# Rev2_Schematic.net
KiCad netlist of a schematic drawn in EasyEDA
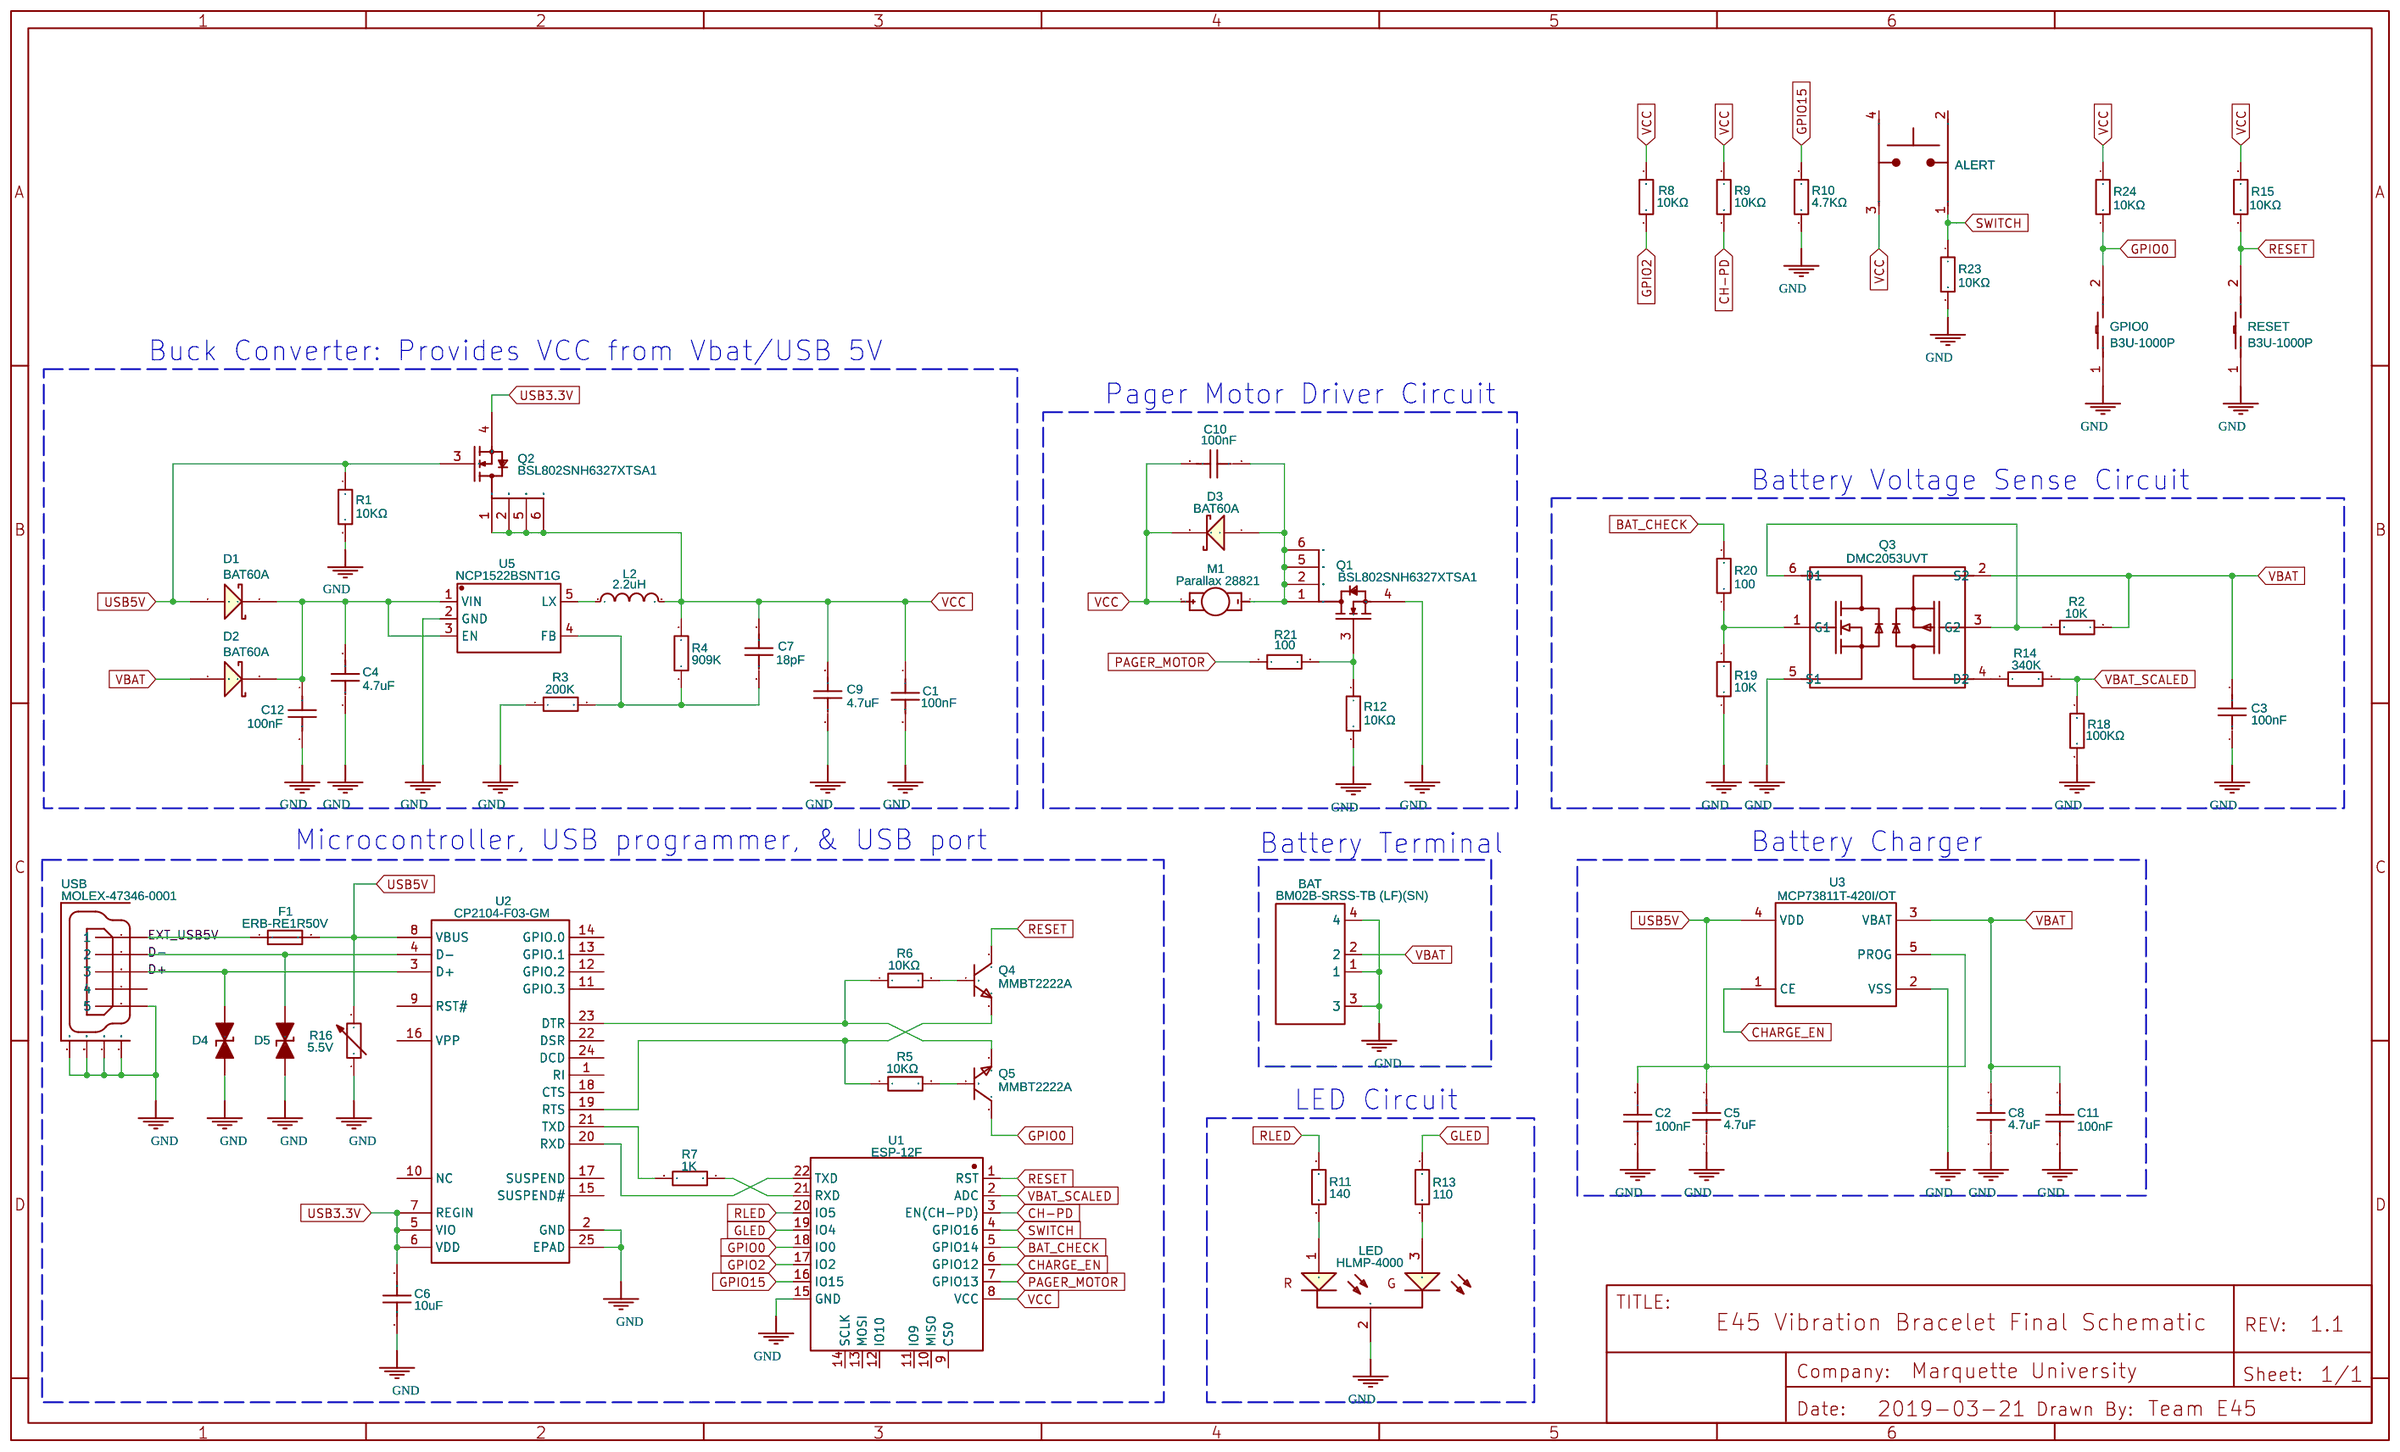
[diagram p0: schematic sheet]

(export (version "E")
  (design (tool "Eeschema 10.0.6"))
  (components
    (comp (ref "ALERT")
      (value "Pushbutton_SMD_SPST_2x2")
      (fields
        (field (name "BOM_Manufacturer Part") "LL3301NF065QG")
        (field (name "BOM_Supplier Part") "612-LL3301NF065QG")
      )
      (libsource (lib "") (part "Unknown_1070_100"))
    )
    (comp (ref "BAT")
      (value "BM02B-SRSS-TB (LF)(SN)")
      (fields
        (field (name "BOM_Manufacturer Part") "BM02B-SRSS-TB(LF)(SN)")
        (field (name "BOM_Supplier Part") "455-1788-1-ND")
      )
      (libsource (lib "") (part "Unknown_725_565"))
    )
    (comp (ref "C1")
      (value "100nF")
      (fields
        (field (name "BOM_Manufacturer Part") "0402YC104KAT2A")
        (field (name "BOM_Supplier Part") "581-0402YC104KAT2A")
      )
      (libsource (lib "") (part "Unknown_485_410"))
    )
    (comp (ref "C2")
      (value "100nF")
      (fields
        (field (name "BOM_Manufacturer Part") "0402YC104KAT2A")
        (field (name "BOM_Supplier Part") "581-0402YC104KAT2A")
      )
      (libsource (lib "") (part "Unknown_910_655"))
    )
    (comp (ref "C3")
      (value "100nF")
      (fields
        (field (name "BOM_Manufacturer Part") "0402YC104KAT2A")
        (field (name "BOM_Supplier Part") "581-0402YC104KAT2A")
      )
      (libsource (lib "") (part "Unknown_1255_420"))
    )
    (comp (ref "C4")
      (value "4.7uF")
      (fields
        (field (name "BOM_Manufacturer Part") "CC0402MRX5R7BB475")
        (field (name "BOM_Supplier Part") "603-CC0402MRX57BB475")
      )
      (libsource (lib "") (part "Unknown_160_400"))
    )
    (comp (ref "C5")
      (value "4.7uF")
      (fields
        (field (name "BOM_Manufacturer Part") "CC0402MRX5R7BB475")
        (field (name "BOM_Supplier Part") "603-CC0402MRX57BB475")
      )
      (libsource (lib "") (part "Unknown_950_655"))
    )
    (comp (ref "C6")
      (value "10uF")
      (fields
        (field (name "BOM_Manufacturer Part") "EMK107BBJ106MA-T")
        (field (name "BOM_Supplier Part") "C90058")
      )
      (libsource (lib "") (part "EMK107BBJ106MA-T"))
    )
    (comp (ref "C7")
      (value "18pF")
      (fields
        (field (name "BOM_Manufacturer Part") "C0402C180M5HACTU")
        (field (name "BOM_Supplier Part") "80-C0402C180M5HACTU")
      )
      (libsource (lib "") (part "Unknown_400_385"))
    )
    (comp (ref "C8")
      (value "4.7uF")
      (fields
        (field (name "BOM_Manufacturer Part") "CC0402MRX5R7BB475")
        (field (name "BOM_Supplier Part") "603-CC0402MRX57BB475")
      )
      (libsource (lib "") (part "Unknown_1115_655"))
    )
    (comp (ref "C9")
      (value "4.7uF")
      (fields
        (field (name "BOM_Manufacturer Part") "CC0402MRX5R7BB475")
        (field (name "BOM_Supplier Part") "603-CC0402MRX57BB475")
      )
      (libsource (lib "") (part "Unknown_440_410"))
    )
    (comp (ref "C10")
      (value "100nF")
      (fields
        (field (name "BOM_Manufacturer Part") "0402YC104KAT2A")
        (field (name "BOM_Supplier Part") "581-0402YC104KAT2A")
      )
      (libsource (lib "") (part "Unknown_665_275"))
    )
    (comp (ref "C11")
      (value "100nF")
      (fields
        (field (name "BOM_Manufacturer Part") "0402YC104KAT2A")
        (field (name "BOM_Supplier Part") "581-0402YC104KAT2A")
      )
      (libsource (lib "") (part "Unknown_1155_655"))
    )
    (comp (ref "C12")
      (value "100nF")
      (fields
        (field (name "BOM_Manufacturer Part") "0402YC104KAT2A")
        (field (name "BOM_Supplier Part") "581-0402YC104KAT2A")
      )
      (libsource (lib "") (part "Unknown_135_420"))
    )
    (comp (ref "D1")
      (value "BAT60A")
      (fields (field (name "BOM_Manufacturer Part") "?"))
      (libsource (lib "") (part "Unknown_95_355"))
    )
    (comp (ref "D2")
      (value "BAT60A")
      (fields (field (name "BOM_Manufacturer Part") "?"))
      (libsource (lib "") (part "Unknown_95_400"))
    )
    (comp (ref "D3")
      (value "BAT60A")
      (fields (field (name "BOM_Manufacturer Part") "?"))
      (libsource (lib "") (part "Unknown_665_315"))
    )
    (comp (ref "D4")
      (value "PGB1010402KR")
      (fields (field (name "BOM_Supplier Part") "C10676"))
      (libsource (lib "") (part "Unknown_90_610"))
    )
    (comp (ref "D5")
      (value "PGB1010402KR")
      (fields (field (name "BOM_Supplier Part") "C10676"))
      (libsource (lib "") (part "Unknown_125_610"))
    )
    (comp (ref "F1")
      (value "ERB-RE1R50V")
      (fields (field (name "BOM_Supplier Part") "667-ERB-RE1R50V"))
      (libsource (lib "") (part "Unknown_125_550"))
    )
    (comp (ref "GPIO0")
      (value "B3U-1000P")
      (fields (field (name "BOM_Supplier Part") "C231329"))
      (libsource (lib "") (part "Unknown_1180_190"))
    )
    (comp (ref "L2")
      (value "2.2uH")
      (fields
        (field (name "BOM_Manufacturer Part") "VLS252015ET-2R2M")
        (field (name "BOM_Supplier Part") "C136232")
      )
      (libsource (lib "") (part "VLS252015ET-2R2M"))
    )
    (comp (ref "LED")
      (value "HLMP-4000")
      (fields (field (name "BOM_Supplier Part") "630-HLMP-4000"))
      (libsource (lib "") (part "Unknown_765_755"))
    )
    (comp (ref "M1")
      (value "Parallax 28821")
      (fields (field (name "BOM_Manufacturer Part") "28821") (field (name "BOM_Supplier Part") "28821-ND"))
      (libsource (lib "") (part "Unknown_665_355"))
    )
    (comp (ref "Q1")
      (value "BSL802SNH6327XTSA1")
      (fields (field (name "BOM_Supplier Part") "726-BSL802SNH6327XTS"))
      (libsource (lib "") (part "Unknown_745_355"))
    )
    (comp (ref "Q2")
      (value "BSL802SNH6327XTSA1")
      (fields (field (name "BOM_Supplier Part") "726-BSL802SNH6327XTS"))
      (libsource (lib "") (part "Unknown_245_275"))
    )
    (comp (ref "Q3")
      (value "DMC2053UVT")
      (fields (field (name "BOM_Supplier Part") "621-DMC2053UVT-7"))
      (libsource (lib "") (part "Unknown_1070_370"))
    )
    (comp (ref "Q4")
      (value "MMBT2222A")
      (fields
        (field (name "BOM_Manufacturer Part") "MMBT2222AWT3G")
        (field (name "BOM_Supplier Part") "MMBT2222AWT3GOSCT-ND")
      )
      (libsource (lib "") (part "Unknown_525_575"))
    )
    (comp (ref "Q5")
      (value "MMBT2222A")
      (fields
        (field (name "BOM_Manufacturer Part") "MMBT2222AWT3G")
        (field (name "BOM_Supplier Part") "MMBT2222AWT3GOSCT-ND")
      )
      (libsource (lib "") (part "Unknown_525_635"))
    )
    (comp (ref "R1")
      (value "10KΩ")
      (fields
        (field (name "BOM_Manufacturer Part") "RM04FTN1002")
        (field (name "BOM_Supplier Part") "C153110")
      )
      (libsource (lib "") (part "RM04FTN1002_1"))
    )
    (comp (ref "R2")
      (value "10K")
      (fields
        (field (name "BOM_Manufacturer Part") "RM04FTN1002")
        (field (name "BOM_Supplier Part") "C153110")
      )
      (libsource (lib "") (part "RM04FTN1002_3"))
    )
    (comp (ref "R3")
      (value "200K")
      (fields
        (field (name "BOM_Manufacturer Part") "AR02BTD2003")
        (field (name "BOM_Supplier Part") "C319777")
      )
      (libsource (lib "") (part "AR02BTD2003"))
    )
    (comp (ref "R4")
      (value "909K")
      (fields
        (field (name "BOM_Manufacturer Part") "AC0402FR-07909KL")
        (field (name "BOM_Supplier Part") "C227267")
      )
      (libsource (lib "") (part "AC0402FR-07909KL"))
    )
    (comp (ref "R5")
      (value "10KΩ")
      (fields
        (field (name "BOM_Manufacturer Part") "RM04FTN1002")
        (field (name "BOM_Supplier Part") "C153110")
      )
      (libsource (lib "") (part "RM04FTN1002"))
    )
    (comp (ref "R6")
      (value "10KΩ")
      (fields
        (field (name "BOM_Manufacturer Part") "RM04FTN1002")
        (field (name "BOM_Supplier Part") "C153110")
      )
      (libsource (lib "") (part "RM04FTN1002"))
    )
    (comp (ref "R7")
      (value "1K")
      (fields
        (field (name "BOM_Manufacturer Part") "ERJ-2RKF1001X")
        (field (name "BOM_Supplier Part") "C192168")
      )
      (libsource (lib "") (part "ERJ-2RKF1001X"))
    )
    (comp (ref "R8")
      (value "10KΩ")
      (fields
        (field (name "BOM_Manufacturer Part") "RM04FTN1002")
        (field (name "BOM_Supplier Part") "C153110")
      )
      (libsource (lib "") (part "RM04FTN1002_1"))
    )
    (comp (ref "R9")
      (value "10KΩ")
      (fields
        (field (name "BOM_Manufacturer Part") "RM04FTN1002")
        (field (name "BOM_Supplier Part") "C153110")
      )
      (libsource (lib "") (part "RM04FTN1002_1"))
    )
    (comp (ref "R10")
      (value "4.7KΩ")
      (fields
        (field (name "BOM_Manufacturer Part") "RS-02K4701FT")
        (field (name "BOM_Supplier Part") "C140158")
      )
      (libsource (lib "") (part "RS-02K4701FT"))
    )
    (comp (ref "R11")
      (value "140")
      (fields
        (field (name "BOM_Manufacturer Part") "AC0402FR-07140RL")
        (field (name "BOM_Supplier Part") "C226782")
      )
      (libsource (lib "") (part "AC0402FR-07140RL"))
    )
    (comp (ref "R12")
      (value "10KΩ")
      (fields
        (field (name "BOM_Manufacturer Part") "RM04FTN1002")
        (field (name "BOM_Supplier Part") "C153110")
      )
      (libsource (lib "") (part "RM04FTN1002_1"))
    )
    (comp (ref "R13")
      (value "110")
      (fields
        (field (name "BOM_Manufacturer Part") "RC0402FR-07110RL")
        (field (name "BOM_Supplier Part") "C138064")
      )
      (libsource (lib "") (part "RC0402FR-07110RL"))
    )
    (comp (ref "R14")
      (value "340K")
      (fields
        (field (name "BOM_Manufacturer Part") "AC0402FR-07340KL")
        (field (name "BOM_Supplier Part") "C227001")
      )
      (libsource (lib "") (part "AC0402FR-07340KL"))
    )
    (comp (ref "R15")
      (value "10KΩ")
      (fields
        (field (name "BOM_Manufacturer Part") "RM04FTN1002")
        (field (name "BOM_Supplier Part") "C153110")
      )
      (libsource (lib "") (part "RM04FTN1002_1"))
    )
    (comp (ref "R16")
      (value "5.5V")
      (fields
        (field (name "BOM_Manufacturer Part") "V5.5MLA0603LNR")
        (field (name "BOM_Supplier Part") "C126845")
      )
      (libsource (lib "") (part "V5.5MLA0603LNR"))
    )
    (comp (ref "R18")
      (value "100KΩ")
      (fields
        (field (name "BOM_Manufacturer Part") "0402WGF1003TCE")
        (field (name "BOM_Supplier Part") "C25741")
      )
      (libsource (lib "") (part "0402WGF1003TCE"))
    )
    (comp (ref "R19")
      (value "10K")
      (fields
        (field (name "BOM_Manufacturer Part") "RM04FTN1002")
        (field (name "BOM_Supplier Part") "C153110")
      )
      (libsource (lib "") (part "RM04FTN1002_2"))
    )
    (comp (ref "R20")
      (value "100")
      (fields
        (field (name "BOM_Manufacturer Part") "RN73H1ETTP1000B25")
        (field (name "BOM_Supplier Part") "C186113")
      )
      (libsource (lib "") (part "RN73H1ETTP1000B25"))
    )
    (comp (ref "R21")
      (value "100")
      (fields
        (field (name "BOM_Manufacturer Part") "RN73H1ETTP1000B25")
        (field (name "BOM_Supplier Part") "C186113")
      )
      (libsource (lib "") (part "RN73H1ETTP1000B25_1"))
    )
    (comp (ref "R23")
      (value "10KΩ")
      (fields
        (field (name "BOM_Manufacturer Part") "RM04FTN1002")
        (field (name "BOM_Supplier Part") "C153110")
      )
      (libsource (lib "") (part "RM04FTN1002_1"))
    )
    (comp (ref "R24")
      (value "10KΩ")
      (fields
        (field (name "BOM_Manufacturer Part") "RM04FTN1002")
        (field (name "BOM_Supplier Part") "C153110")
      )
      (libsource (lib "") (part "RM04FTN1002_1"))
    )
    (comp (ref "RESET")
      (value "B3U-1000P")
      (fields (field (name "BOM_Supplier Part") "C231329"))
      (libsource (lib "") (part "Unknown_1260_190"))
    )
    (comp (ref "U1")
      (value "ESP-12F")
      (fields
        (field (name "BOM_Manufacturer Part") "ESP-12F(ESP8266MOD)")
        (field (name "BOM_Supplier Part") "B01M4IOFIT")
      )
      (libsource (lib "") (part "Unknown_480_740"))
    )
    (comp (ref "U2")
      (value "CP2104-F03-GM")
      (fields (field (name "BOM_Supplier Part") "C47742"))
      (libsource (lib "") (part "Unknown_250_640"))
    )
    (comp (ref "U3")
      (value "MCP73811T-420I/OT")
      (fields (field (name "BOM_Supplier Part") "C145381"))
      (libsource (lib "") (part "Unknown_1025_560"))
    )
    (comp (ref "U5")
      (value "NCP1522BSNT1G")
      (fields (field (name "BOM_Supplier Part") "C231821"))
      (libsource (lib "") (part "Unknown_255_365"))
    )
    (comp (ref "USB")
      (value "MOLEX-47346-0001")
      (fields (field (name "BOM_Manufacturer Part") "?"))
      (libsource (lib "") (part "Unknown_20_575"))
    )
  )
  (nets
    (net (code "1") (name "/D+") (class "Default")
      (node (ref "D4") (pin "1") (pinfunction "K_1") (pintype "unspecified"))
      (node (ref "U2") (pin "3") (pinfunction "D+_3") (pintype "bidirectional"))
      (node (ref "USB") (pin "3") (pinfunction "3_3") (pintype "input"))
    )
    (net (code "2") (name "/D-") (class "Default")
      (node (ref "D5") (pin "1") (pinfunction "K_1") (pintype "unspecified"))
      (node (ref "U2") (pin "4") (pinfunction "D-_4") (pintype "bidirectional"))
      (node (ref "USB") (pin "2") (pinfunction "2_2") (pintype "input"))
    )
    (net (code "3") (name "/EXT_USB5V") (class "Default")
      (node (ref "F1") (pin "1") (pinfunction "1_1") (pintype "unspecified"))
      (node (ref "USB") (pin "1") (pinfunction "1_1") (pintype "input"))
    )
    (net (code "4") (name "BAT_CHECK") (class "Default")
      (node (ref "R20") (pin "2") (pinfunction "2_2") (pintype "unspecified"))
      (node (ref "U1") (pin "5") (pinfunction "GPIO14_5") (pintype "unspecified"))
    )
    (net (code "5") (name "CH-PD") (class "Default")
      (node (ref "R9") (pin "2") (pinfunction "2_2") (pintype "input"))
      (node (ref "U1") (pin "3") (pinfunction "EN(CH-PD)_3") (pintype "unspecified"))
    )
    (net (code "6") (name "CHARGE_EN") (class "Default")
      (node (ref "U1") (pin "6") (pinfunction "GPIO12_6") (pintype "unspecified"))
      (node (ref "U3") (pin "1") (pinfunction "CE_1") (pintype "unspecified"))
    )
    (net (code "7") (name "GLED") (class "Default")
      (node (ref "R13") (pin "2") (pinfunction "2_2") (pintype "input"))
      (node (ref "U1") (pin "19") (pinfunction "IO4_19") (pintype "unspecified"))
    )
    (net (code "8") (name "GND") (class "Default")
      (node (ref "BAT") (pin "1") (pinfunction "1_1") (pintype "unspecified"))
      (node (ref "BAT") (pin "3") (pinfunction "3_3") (pintype "unspecified"))
      (node (ref "BAT") (pin "4") (pinfunction "4_4") (pintype "unspecified"))
      (node (ref "C1") (pin "2") (pinfunction "2_2") (pintype "unspecified"))
      (node (ref "C11") (pin "2") (pinfunction "2_2") (pintype "unspecified"))
      (node (ref "C12") (pin "2") (pinfunction "2_2") (pintype "unspecified"))
      (node (ref "C2") (pin "2") (pinfunction "2_2") (pintype "unspecified"))
      (node (ref "C3") (pin "1") (pinfunction "1_1") (pintype "unspecified"))
      (node (ref "C4") (pin "1") (pinfunction "1_1") (pintype "unspecified"))
      (node (ref "C5") (pin "1") (pinfunction "1_1") (pintype "unspecified"))
      (node (ref "C6") (pin "1") (pinfunction "1_1") (pintype "unspecified"))
      (node (ref "C8") (pin "1") (pinfunction "1_1") (pintype "unspecified"))
      (node (ref "C9") (pin "1") (pinfunction "1_1") (pintype "unspecified"))
      (node (ref "D4") (pin "2") (pinfunction "A_2") (pintype "unspecified"))
      (node (ref "D5") (pin "2") (pinfunction "A_2") (pintype "unspecified"))
      (node (ref "GPIO0") (pin "1") (pinfunction "1_1") (pintype "unspecified"))
      (node (ref "LED") (pin "2") (pinfunction "B_2") (pintype "passive"))
      (node (ref "Q1") (pin "4") (pinfunction "Source_4") (pintype "unspecified"))
      (node (ref "Q3") (pin "5") (pinfunction "S1_5") (pintype "unspecified"))
      (node (ref "R1") (pin "2") (pinfunction "2_2") (pintype "input"))
      (node (ref "R10") (pin "1") (pinfunction "1_1") (pintype "input"))
      (node (ref "R12") (pin "2") (pinfunction "2_2") (pintype "input"))
      (node (ref "R16") (pin "1") (pinfunction "1_1") (pintype "unspecified"))
      (node (ref "R18") (pin "2") (pinfunction "2_2") (pintype "input"))
      (node (ref "R19") (pin "1") (pinfunction "1_1") (pintype "input"))
      (node (ref "R23") (pin "2") (pinfunction "2_2") (pintype "input"))
      (node (ref "R3") (pin "1") (pinfunction "1_1") (pintype "unspecified"))
      (node (ref "RESET") (pin "1") (pinfunction "1_1") (pintype "unspecified"))
      (node (ref "U1") (pin "15") (pinfunction "GND_15") (pintype "unspecified"))
      (node (ref "U2") (pin "2") (pinfunction "GND_2") (pintype "passive"))
      (node (ref "U2") (pin "25") (pinfunction "EPAD_25") (pintype "passive"))
      (node (ref "U3") (pin "2") (pinfunction "VSS_2") (pintype "passive"))
      (node (ref "U5") (pin "2") (pinfunction "GND_2") (pintype "unspecified"))
      (node (ref "USB") (pin "5") (pinfunction "5_5") (pintype "input"))
      (node (ref "USB") (pin "GND1") (pinfunction "GND1_GND1") (pintype "unspecified"))
      (node (ref "USB") (pin "GND2") (pinfunction "GND2_GND2") (pintype "unspecified"))
      (node (ref "USB") (pin "GND3") (pinfunction "GND3_GND3") (pintype "unspecified"))
      (node (ref "USB") (pin "GND4") (pinfunction "GND4_GND4") (pintype "unspecified"))
    )
    (net (code "9") (name "GPIO0") (class "Default")
      (node (ref "GPIO0") (pin "2") (pinfunction "2_2") (pintype "unspecified"))
      (node (ref "Q5") (pin "3") (pinfunction "C_3") (pintype "unspecified"))
      (node (ref "R24") (pin "2") (pinfunction "2_2") (pintype "input"))
      (node (ref "U1") (pin "18") (pinfunction "IO0_18") (pintype "unspecified"))
    )
    (net (code "10") (name "GPIO2") (class "Default")
      (node (ref "R8") (pin "2") (pinfunction "2_2") (pintype "input"))
      (node (ref "U1") (pin "17") (pinfunction "IO2_17") (pintype "unspecified"))
    )
    (net (code "11") (name "GPIO15") (class "Default")
      (node (ref "R10") (pin "2") (pinfunction "2_2") (pintype "input"))
      (node (ref "U1") (pin "16") (pinfunction "IO15_16") (pintype "unspecified"))
    )
    (net (code "12") (name "Net-(D1-K)") (class "Default")
      (node (ref "C12") (pin "1") (pinfunction "1_1") (pintype "unspecified"))
      (node (ref "C4") (pin "2") (pinfunction "2_2") (pintype "unspecified"))
      (node (ref "D1") (pin "2") (pinfunction "K_2") (pintype "unspecified"))
      (node (ref "D2") (pin "2") (pinfunction "K_2") (pintype "unspecified"))
      (node (ref "U5") (pin "1") (pinfunction "VIN_1") (pintype "unspecified"))
      (node (ref "U5") (pin "3") (pinfunction "EN_3") (pintype "unspecified"))
    )
    (net (code "13") (name "Net-(D3-A)") (class "Default")
      (node (ref "C10") (pin "1") (pinfunction "1_1") (pintype "unspecified"))
      (node (ref "D3") (pin "1") (pinfunction "A_1") (pintype "unspecified"))
      (node (ref "M1") (pin "-") (pinfunction "-_-") (pintype "unspecified"))
      (node (ref "Q1") (pin "1") (pinfunction "Drain_1") (pintype "unspecified"))
      (node (ref "Q1") (pin "2") (pinfunction "Drain_2") (pintype "unspecified"))
      (node (ref "Q1") (pin "5") (pinfunction "Drain_5") (pintype "unspecified"))
      (node (ref "Q1") (pin "6") (pinfunction "Drain_6") (pintype "unspecified"))
    )
    (net (code "14") (name "Net-(LED-A)") (class "Default")
      (node (ref "LED") (pin "1") (pinfunction "A_1") (pintype "passive"))
      (node (ref "R11") (pin "1") (pinfunction "1_1") (pintype "unspecified"))
    )
    (net (code "15") (name "Net-(LED-C)") (class "Default")
      (node (ref "LED") (pin "3") (pinfunction "C_3") (pintype "passive"))
      (node (ref "R13") (pin "1") (pinfunction "1_1") (pintype "input"))
    )
    (net (code "16") (name "Net-(Q1-Gate)") (class "Default")
      (node (ref "Q1") (pin "3") (pinfunction "Gate_3") (pintype "unspecified"))
      (node (ref "R12") (pin "1") (pinfunction "1_1") (pintype "input"))
      (node (ref "R21") (pin "2") (pinfunction "2_2") (pintype "unspecified"))
    )
    (net (code "17") (name "Net-(Q3-D1)") (class "Default")
      (node (ref "Q3") (pin "3") (pinfunction "G2_3") (pintype "unspecified"))
      (node (ref "Q3") (pin "6") (pinfunction "D1_6") (pintype "unspecified"))
      (node (ref "R2") (pin "2") (pinfunction "2_2") (pintype "input"))
    )
    (net (code "18") (name "Net-(Q3-D2)") (class "Default")
      (node (ref "Q3") (pin "4") (pinfunction "D2_4") (pintype "unspecified"))
      (node (ref "R14") (pin "1") (pinfunction "1_1") (pintype "unspecified"))
    )
    (net (code "19") (name "Net-(Q3-G1)") (class "Default")
      (node (ref "Q3") (pin "1") (pinfunction "G1_1") (pintype "unspecified"))
      (node (ref "R19") (pin "2") (pinfunction "2_2") (pintype "input"))
      (node (ref "R20") (pin "1") (pinfunction "1_1") (pintype "unspecified"))
    )
    (net (code "20") (name "Net-(Q4-B)") (class "Default")
      (node (ref "Q4") (pin "1") (pinfunction "B_1") (pintype "unspecified"))
      (node (ref "R6") (pin "2") (pinfunction "2_2") (pintype "input"))
    )
    (net (code "21") (name "Net-(Q4-E)") (class "Default")
      (node (ref "Q4") (pin "2") (pinfunction "E_2") (pintype "unspecified"))
      (node (ref "R5") (pin "1") (pinfunction "1_1") (pintype "input"))
      (node (ref "U2") (pin "19") (pinfunction "RTS_19") (pintype "output"))
    )
    (net (code "22") (name "Net-(Q5-B)") (class "Default")
      (node (ref "Q5") (pin "1") (pinfunction "B_1") (pintype "unspecified"))
      (node (ref "R5") (pin "2") (pinfunction "2_2") (pintype "input"))
    )
    (net (code "23") (name "Net-(Q5-E)") (class "Default")
      (node (ref "Q5") (pin "2") (pinfunction "E_2") (pintype "unspecified"))
      (node (ref "R6") (pin "1") (pinfunction "1_1") (pintype "input"))
      (node (ref "U2") (pin "23") (pinfunction "DTR_23") (pintype "output"))
    )
    (net (code "24") (name "Net-(U1-RXD)") (class "Default")
      (node (ref "R7") (pin "2") (pinfunction "2_2") (pintype "unspecified"))
      (node (ref "U1") (pin "21") (pinfunction "RXD_21") (pintype "unspecified"))
    )
    (net (code "25") (name "Net-(U1-TXD)") (class "Default")
      (node (ref "U1") (pin "22") (pinfunction "TXD_22") (pintype "unspecified"))
      (node (ref "U2") (pin "20") (pinfunction "RXD_20") (pintype "unspecified"))
    )
    (net (code "26") (name "Net-(U2-TXD)") (class "Default")
      (node (ref "R7") (pin "1") (pinfunction "1_1") (pintype "unspecified"))
      (node (ref "U2") (pin "21") (pinfunction "TXD_21") (pintype "output"))
    )
    (net (code "27") (name "Net-(U5-FB)") (class "Default")
      (node (ref "C7") (pin "1") (pinfunction "1_1") (pintype "unspecified"))
      (node (ref "R3") (pin "2") (pinfunction "2_2") (pintype "unspecified"))
      (node (ref "R4") (pin "1") (pinfunction "1_1") (pintype "unspecified"))
      (node (ref "U5") (pin "4") (pinfunction "FB_4") (pintype "unspecified"))
    )
    (net (code "28") (name "Net-(U5-LX)") (class "Default")
      (node (ref "L2") (pin "1") (pinfunction "1_1") (pintype "unspecified"))
      (node (ref "U5") (pin "5") (pinfunction "LX_5") (pintype "unspecified"))
    )
    (net (code "29") (name "PAGER_MOTOR") (class "Default")
      (node (ref "R21") (pin "1") (pinfunction "1_1") (pintype "unspecified"))
      (node (ref "U1") (pin "7") (pinfunction "GPIO13_7") (pintype "unspecified"))
    )
    (net (code "30") (name "RESET") (class "Default")
      (node (ref "Q4") (pin "3") (pinfunction "C_3") (pintype "unspecified"))
      (node (ref "R15") (pin "2") (pinfunction "2_2") (pintype "input"))
      (node (ref "RESET") (pin "2") (pinfunction "2_2") (pintype "unspecified"))
      (node (ref "U1") (pin "1") (pinfunction "RST_1") (pintype "unspecified"))
    )
    (net (code "31") (name "RLED") (class "Default")
      (node (ref "R11") (pin "2") (pinfunction "2_2") (pintype "unspecified"))
      (node (ref "U1") (pin "20") (pinfunction "IO5_20") (pintype "unspecified"))
    )
    (net (code "32") (name "SWITCH") (class "Default")
      (node (ref "ALERT") (pin "1") (pinfunction "1_1") (pintype "unspecified"))
      (node (ref "R23") (pin "1") (pinfunction "1_1") (pintype "input"))
      (node (ref "U1") (pin "4") (pinfunction "GPIO16_4") (pintype "unspecified"))
    )
    (net (code "33") (name "USB3.3V") (class "Default")
      (node (ref "C6") (pin "2") (pinfunction "2_2") (pintype "unspecified"))
      (node (ref "Q2") (pin "4") (pinfunction "Source_4") (pintype "unspecified"))
      (node (ref "U2") (pin "5") (pinfunction "VIO_5") (pintype "passive"))
      (node (ref "U2") (pin "6") (pinfunction "VDD_6") (pintype "passive"))
      (node (ref "U2") (pin "7") (pinfunction "REGIN_7") (pintype "passive"))
    )
    (net (code "34") (name "USB5V") (class "Default")
      (node (ref "C2") (pin "1") (pinfunction "1_1") (pintype "unspecified"))
      (node (ref "C5") (pin "2") (pinfunction "2_2") (pintype "unspecified"))
      (node (ref "D1") (pin "1") (pinfunction "A_1") (pintype "unspecified"))
      (node (ref "F1") (pin "2") (pinfunction "2_2") (pintype "unspecified"))
      (node (ref "Q2") (pin "3") (pinfunction "Gate_3") (pintype "unspecified"))
      (node (ref "R1") (pin "1") (pinfunction "1_1") (pintype "input"))
      (node (ref "R16") (pin "2") (pinfunction "2_2") (pintype "unspecified"))
      (node (ref "U2") (pin "8") (pinfunction "VBUS_8") (pintype "unspecified"))
      (node (ref "U3") (pin "4") (pinfunction "VDD_4") (pintype "passive"))
      (node (ref "U3") (pin "5") (pinfunction "PROG_5") (pintype "unspecified"))
    )
    (net (code "35") (name "VBAT") (class "Default")
      (node (ref "BAT") (pin "2") (pinfunction "2_2") (pintype "unspecified"))
      (node (ref "C11") (pin "1") (pinfunction "1_1") (pintype "unspecified"))
      (node (ref "C3") (pin "2") (pinfunction "2_2") (pintype "unspecified"))
      (node (ref "C8") (pin "2") (pinfunction "2_2") (pintype "unspecified"))
      (node (ref "D2") (pin "1") (pinfunction "A_1") (pintype "unspecified"))
      (node (ref "Q3") (pin "2") (pinfunction "S2_2") (pintype "unspecified"))
      (node (ref "R2") (pin "1") (pinfunction "1_1") (pintype "input"))
      (node (ref "U3") (pin "3") (pinfunction "VBAT_3") (pintype "passive"))
    )
    (net (code "36") (name "VBAT_SCALED") (class "Default")
      (node (ref "R14") (pin "2") (pinfunction "2_2") (pintype "unspecified"))
      (node (ref "R18") (pin "1") (pinfunction "1_1") (pintype "input"))
      (node (ref "U1") (pin "2") (pinfunction "ADC_2") (pintype "unspecified"))
    )
    (net (code "37") (name "VCC") (class "Default")
      (node (ref "ALERT") (pin "3") (pinfunction "3_3") (pintype "unspecified"))
      (node (ref "C1") (pin "1") (pinfunction "1_1") (pintype "unspecified"))
      (node (ref "C10") (pin "2") (pinfunction "2_2") (pintype "unspecified"))
      (node (ref "C7") (pin "2") (pinfunction "2_2") (pintype "unspecified"))
      (node (ref "C9") (pin "2") (pinfunction "2_2") (pintype "unspecified"))
      (node (ref "D3") (pin "2") (pinfunction "K_2") (pintype "unspecified"))
      (node (ref "L2") (pin "2") (pinfunction "2_2") (pintype "unspecified"))
      (node (ref "M1") (pin "+") (pinfunction "+_+") (pintype "unspecified"))
      (node (ref "Q2") (pin "1") (pinfunction "Drain_1") (pintype "unspecified"))
      (node (ref "Q2") (pin "2") (pinfunction "Drain_2") (pintype "unspecified"))
      (node (ref "Q2") (pin "5") (pinfunction "Drain_5") (pintype "unspecified"))
      (node (ref "Q2") (pin "6") (pinfunction "Drain_6") (pintype "unspecified"))
      (node (ref "R15") (pin "1") (pinfunction "1_1") (pintype "input"))
      (node (ref "R24") (pin "1") (pinfunction "1_1") (pintype "input"))
      (node (ref "R4") (pin "2") (pinfunction "2_2") (pintype "unspecified"))
      (node (ref "R8") (pin "1") (pinfunction "1_1") (pintype "input"))
      (node (ref "R9") (pin "1") (pinfunction "1_1") (pintype "input"))
      (node (ref "U1") (pin "8") (pinfunction "VCC_8") (pintype "unspecified"))
    )
    (net (code "38") (name "unconnected-(ALERT-Pad2)") (class "Default")
      (node (ref "ALERT") (pin "2") (pinfunction "2_2") (pintype "unspecified"))
    )
    (net (code "39") (name "unconnected-(ALERT-Pad4)") (class "Default")
      (node (ref "ALERT") (pin "4") (pinfunction "4_4") (pintype "unspecified"))
    )
    (net (code "40") (name "unconnected-(U1-CS0-Pad9)") (class "Default")
      (node (ref "U1") (pin "9") (pinfunction "CS0_9") (pintype "unspecified"))
    )
    (net (code "41") (name "unconnected-(U1-IO9-Pad11)") (class "Default")
      (node (ref "U1") (pin "11") (pinfunction "IO9_11") (pintype "unspecified"))
    )
    (net (code "42") (name "unconnected-(U1-IO10-Pad12)") (class "Default")
      (node (ref "U1") (pin "12") (pinfunction "IO10_12") (pintype "unspecified"))
    )
    (net (code "43") (name "unconnected-(U1-MISO-Pad10)") (class "Default")
      (node (ref "U1") (pin "10") (pinfunction "MISO_10") (pintype "unspecified"))
    )
    (net (code "44") (name "unconnected-(U1-MOSI-Pad13)") (class "Default")
      (node (ref "U1") (pin "13") (pinfunction "MOSI_13") (pintype "unspecified"))
    )
    (net (code "45") (name "unconnected-(U1-SCLK-Pad14)") (class "Default")
      (node (ref "U1") (pin "14") (pinfunction "SCLK_14") (pintype "unspecified"))
    )
    (net (code "46") (name "unconnected-(U2-CTS-Pad18)") (class "Default")
      (node (ref "U2") (pin "18") (pinfunction "CTS_18") (pintype "unspecified"))
    )
    (net (code "47") (name "unconnected-(U2-DCD-Pad24)") (class "Default")
      (node (ref "U2") (pin "24") (pinfunction "DCD_24") (pintype "unspecified"))
    )
    (net (code "48") (name "unconnected-(U2-DSR-Pad22)") (class "Default")
      (node (ref "U2") (pin "22") (pinfunction "DSR_22") (pintype "unspecified"))
    )
    (net (code "49") (name "unconnected-(U2-GPIO.0-Pad14)") (class "Default")
      (node (ref "U2") (pin "14") (pinfunction "GPIO.0_14") (pintype "bidirectional"))
    )
    (net (code "50") (name "unconnected-(U2-GPIO.1-Pad13)") (class "Default")
      (node (ref "U2") (pin "13") (pinfunction "GPIO.1_13") (pintype "bidirectional"))
    )
    (net (code "51") (name "unconnected-(U2-GPIO.2-Pad12)") (class "Default")
      (node (ref "U2") (pin "12") (pinfunction "GPIO.2_12") (pintype "bidirectional"))
    )
    (net (code "52") (name "unconnected-(U2-GPIO.3-Pad11)") (class "Default")
      (node (ref "U2") (pin "11") (pinfunction "GPIO.3_11") (pintype "bidirectional"))
    )
    (net (code "53") (name "unconnected-(U2-NC-Pad10)") (class "Default")
      (node (ref "U2") (pin "10") (pinfunction "NC_10") (pintype "unspecified"))
    )
    (net (code "54") (name "unconnected-(U2-RI-Pad1)") (class "Default")
      (node (ref "U2") (pin "1") (pinfunction "RI_1") (pintype "unspecified"))
    )
    (net (code "55") (name "unconnected-(U2-RST#-Pad9)") (class "Default")
      (node (ref "U2") (pin "9") (pinfunction "RST#_9") (pintype "bidirectional"))
    )
    (net (code "56") (name "unconnected-(U2-SUSPEND#-Pad15)") (class "Default")
      (node (ref "U2") (pin "15") (pinfunction "SUSPEND#_15") (pintype "output"))
    )
    (net (code "57") (name "unconnected-(U2-SUSPEND-Pad17)") (class "Default")
      (node (ref "U2") (pin "17") (pinfunction "SUSPEND_17") (pintype "output"))
    )
    (net (code "58") (name "unconnected-(U2-VPP-Pad16)") (class "Default")
      (node (ref "U2") (pin "16") (pinfunction "VPP_16") (pintype "unspecified"))
    )
    (net (code "59") (name "unconnected-(USB-Pad4)") (class "Default")
      (node (ref "USB") (pin "4") (pinfunction "4_4") (pintype "input"))
    )
  )
)
